# THIEA3000_LIGHTING_BOARD_V2-2.net
KiCad netlist of a schematic drawn in Altium Designer
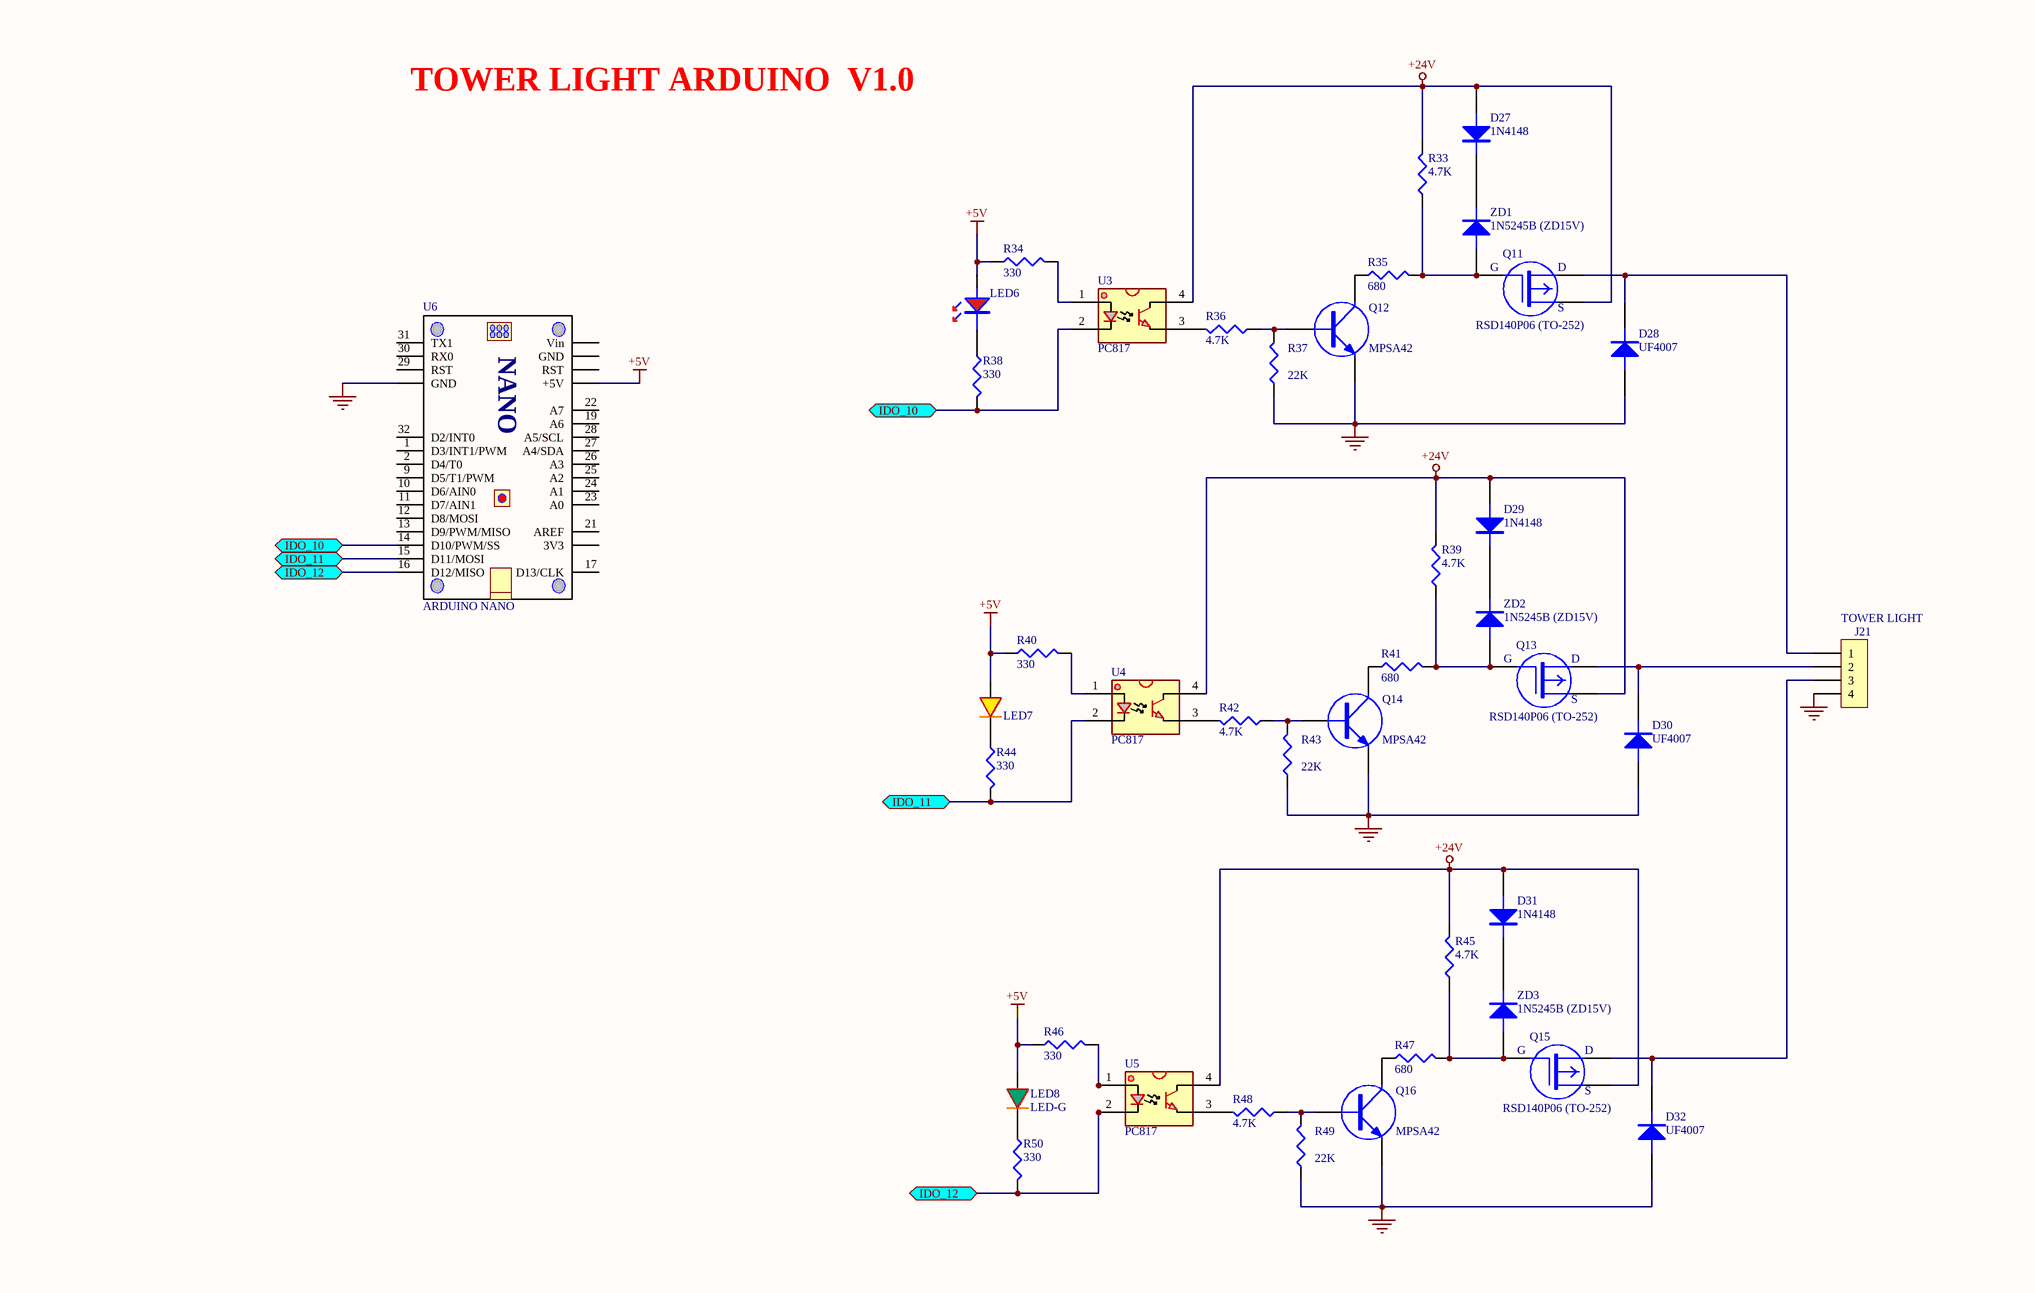
[diagram p0: THIEA3000 LIGHTING BOARD V2-2.SchDoc]

(export (version "E")
  (design (tool "Eeschema 10.0.6"))
  (components
    (comp (ref "D27")
      (value "1N4148")
      (footprint "DIODE 8.5")
      (description "Diode")
      (libsource (lib "*") (part "DIODE"))
    )
    (comp (ref "D28")
      (value "UF4007")
      (footprint "diode 13.0")
      (description "0029-0179-1")
      (libsource (lib "*") (part "DIODE"))
    )
    (comp (ref "D29")
      (value "1N4148")
      (footprint "DIODE 8.5")
      (description "Diode")
      (libsource (lib "*") (part "DIODE"))
    )
    (comp (ref "D30")
      (value "UF4007")
      (footprint "diode 13.0")
      (description "0029-0179-1")
      (libsource (lib "*") (part "DIODE"))
    )
    (comp (ref "D31")
      (value "1N4148")
      (footprint "DIODE 8.5")
      (description "Diode")
      (libsource (lib "*") (part "DIODE"))
    )
    (comp (ref "D32")
      (value "UF4007")
      (footprint "diode 13.0")
      (description "0029-0179-1")
      (libsource (lib "*") (part "DIODE"))
    )
    (comp (ref "J21")
      (value "TOWER LIGHT")
      (footprint "Plug-in TERM 5.0/4P/R")
      (description "0005-0012-5")
      (libsource (lib "*") (part "CON4"))
    )
    (comp (ref "LED6")
      (value "~")
      (footprint "LED 3/2.54/R")
      (description "0302-0042-3")
      (libsource (lib "*") (part "LED-R"))
    )
    (comp (ref "LED7")
      (value "LED-Y")
      (footprint "LED 3/2.54/R")
      (description "0686-0022-4")
      (libsource (lib "Support Project") (part "LED-Y"))
    )
    (comp (ref "LED8")
      (value "LED-G")
      (footprint "LED 5/2.54/R")
      (description "0302-0001-4")
      (libsource (lib "Support Project") (part "LED-G"))
    )
    (comp (ref "Q11")
      (value "RSD140P06 (TO-252)")
      (footprint "TO-252-3")
      (description "0176-0392-4")
      (libsource (lib "*") (part "MOSFET-P1"))
    )
    (comp (ref "Q12")
      (value "MPSA42")
      (footprint "TO-92")
      (description "0123-0670-5")
      (fields (field (name "ALTIUM_UNNAMED_1") "MPSA42"))
      (libsource (lib "*") (part "NPN"))
    )
    (comp (ref "Q13")
      (value "RSD140P06 (TO-252)")
      (footprint "TO-252-3")
      (description "0176-0392-4")
      (libsource (lib "*") (part "MOSFET-P1"))
    )
    (comp (ref "Q14")
      (value "MPSA42")
      (footprint "TO-92")
      (description "0123-0670-5")
      (fields (field (name "ALTIUM_UNNAMED_1") "MPSA42"))
      (libsource (lib "*") (part "NPN"))
    )
    (comp (ref "Q15")
      (value "RSD140P06 (TO-252)")
      (footprint "TO-252-3")
      (description "0176-0392-4")
      (libsource (lib "*") (part "MOSFET-P1"))
    )
    (comp (ref "Q16")
      (value "MPSA42")
      (footprint "TO-92")
      (description "0123-0670-5")
      (fields (field (name "ALTIUM_UNNAMED_1") "MPSA42"))
      (libsource (lib "*") (part "NPN"))
    )
    (comp (ref "R33")
      (value "22K")
      (footprint "RES 1/4")
      (fields (field (name "ALTIUM_UNNAMED_1") "4.7K"))
      (libsource (lib "*") (part "RES1"))
    )
    (comp (ref "R34")
      (value "22K")
      (footprint "RES 1/4")
      (fields (field (name "ALTIUM_UNNAMED_1") "330"))
      (libsource (lib "*") (part "RES1"))
    )
    (comp (ref "R35") (value "680") (footprint "RES 1/4") (libsource (lib "*") (part "RES1")))
    (comp (ref "R36")
      (value "22K")
      (footprint "RES 1/4")
      (fields (field (name "ALTIUM_UNNAMED_1") "4.7K"))
      (libsource (lib "*") (part "RES1"))
    )
    (comp (ref "R37")
      (value "22K")
      (footprint "RES 1/4")
      (fields (field (name "ALTIUM_UNNAMED_1") "22K"))
      (libsource (lib "*") (part "RES1"))
    )
    (comp (ref "R38")
      (value "22K")
      (footprint "RES 1/4")
      (fields (field (name "ALTIUM_UNNAMED_1") "330"))
      (libsource (lib "*") (part "RES1"))
    )
    (comp (ref "R39")
      (value "22K")
      (footprint "RES 1/4")
      (fields (field (name "ALTIUM_UNNAMED_1") "4.7K"))
      (libsource (lib "*") (part "RES1"))
    )
    (comp (ref "R40")
      (value "22K")
      (footprint "RES 1/4")
      (fields (field (name "ALTIUM_UNNAMED_1") "330"))
      (libsource (lib "*") (part "RES1"))
    )
    (comp (ref "R41") (value "680") (footprint "RES 1/4") (libsource (lib "*") (part "RES1")))
    (comp (ref "R42")
      (value "22K")
      (footprint "RES 1/4")
      (fields (field (name "ALTIUM_UNNAMED_1") "4.7K"))
      (libsource (lib "*") (part "RES1"))
    )
    (comp (ref "R43")
      (value "22K")
      (footprint "RES 1/4")
      (fields (field (name "ALTIUM_UNNAMED_1") "22K"))
      (libsource (lib "*") (part "RES1"))
    )
    (comp (ref "R44")
      (value "22K")
      (footprint "RES 1/4")
      (fields (field (name "ALTIUM_UNNAMED_1") "330"))
      (libsource (lib "*") (part "RES1"))
    )
    (comp (ref "R45")
      (value "22K")
      (footprint "RES 1/4")
      (fields (field (name "ALTIUM_UNNAMED_1") "4.7K"))
      (libsource (lib "*") (part "RES1"))
    )
    (comp (ref "R46")
      (value "22K")
      (footprint "RES 1/4")
      (fields (field (name "ALTIUM_UNNAMED_1") "330"))
      (libsource (lib "*") (part "RES1"))
    )
    (comp (ref "R47") (value "680") (footprint "RES 1/4") (libsource (lib "*") (part "RES1")))
    (comp (ref "R48")
      (value "22K")
      (footprint "RES 1/4")
      (fields (field (name "ALTIUM_UNNAMED_1") "4.7K"))
      (libsource (lib "*") (part "RES1"))
    )
    (comp (ref "R49")
      (value "22K")
      (footprint "RES 1/4")
      (fields (field (name "ALTIUM_UNNAMED_1") "22K"))
      (libsource (lib "*") (part "RES1"))
    )
    (comp (ref "R50")
      (value "22K")
      (footprint "RES 1/4")
      (fields (field (name "ALTIUM_UNNAMED_1") "330"))
      (libsource (lib "*") (part "RES1"))
    )
    (comp (ref "U3")
      (value "PC817")
      (footprint "DIP-4L")
      (libsource (lib "Support Project") (part "OPTO TRANSISTOR"))
    )
    (comp (ref "U4")
      (value "PC817")
      (footprint "DIP-4L")
      (libsource (lib "Support Project") (part "OPTO TRANSISTOR"))
    )
    (comp (ref "U5")
      (value "PC817")
      (footprint "DIP-4L")
      (libsource (lib "Support Project") (part "OPTO TRANSISTOR"))
    )
    (comp (ref "U6")
      (value "ARDUINO NANO")
      (footprint "ARDUINO Nano")
      (libsource (lib "Support Project") (part "ARDUINO NANO"))
    )
    (comp (ref "ZD1")
      (value "1N5245B (ZD15V)")
      (footprint "DIODE 8.5")
      (description "0135-0081-3")
      (libsource (lib "*") (part "DIODE"))
    )
    (comp (ref "ZD2")
      (value "1N5245B (ZD15V)")
      (footprint "DIODE 8.5")
      (description "0135-0081-3")
      (libsource (lib "*") (part "DIODE"))
    )
    (comp (ref "ZD3")
      (value "1N5245B (ZD15V)")
      (footprint "DIODE 8.5")
      (description "0135-0081-3")
      (libsource (lib "*") (part "DIODE"))
    )
  )
  (nets
    (net (code "1") (name "+5V") (class "Default")
      (node (ref "LED6") (pin "A") (pintype "passive"))
      (node (ref "LED7") (pin "A") (pinfunction "A_A") (pintype "passive"))
      (node (ref "LED8") (pin "A") (pinfunction "A_A") (pintype "passive"))
      (node (ref "R34") (pin "1") (pintype "passive"))
      (node (ref "R40") (pin "1") (pintype "passive"))
      (node (ref "R46") (pin "1") (pintype "passive"))
      (node (ref "U6") (pin "+5V") (pinfunction "+5V_+5V") (pintype "passive"))
    )
    (net (code "2") (name "+24V") (class "Default")
      (node (ref "D27") (pin "1") (pinfunction "A_1") (pintype "passive"))
      (node (ref "D29") (pin "1") (pinfunction "A_1") (pintype "passive"))
      (node (ref "D31") (pin "1") (pinfunction "A_1") (pintype "passive"))
      (node (ref "Q11") (pin "2") (pinfunction "D_2") (pintype "passive"))
      (node (ref "Q13") (pin "2") (pinfunction "D_2") (pintype "passive"))
      (node (ref "Q15") (pin "2") (pinfunction "D_2") (pintype "passive"))
      (node (ref "R33") (pin "2") (pintype "passive"))
      (node (ref "R39") (pin "2") (pintype "passive"))
      (node (ref "R45") (pin "2") (pintype "passive"))
      (node (ref "U3") (pin "4") (pinfunction "C_4") (pintype "passive"))
      (node (ref "U4") (pin "4") (pinfunction "C_4") (pintype "passive"))
      (node (ref "U5") (pin "4") (pinfunction "C_4") (pintype "passive"))
    )
    (net (code "3") (name "/IDO_10") (class "Default")
      (node (ref "R38") (pin "2") (pintype "passive"))
      (node (ref "U3") (pin "2") (pinfunction "K_2") (pintype "passive"))
      (node (ref "U6") (pin "14") (pinfunction "D10/PWM/SS_14") (pintype "passive"))
    )
    (net (code "4") (name "/IDO_11") (class "Default")
      (node (ref "R44") (pin "2") (pintype "passive"))
      (node (ref "U4") (pin "2") (pinfunction "K_2") (pintype "passive"))
      (node (ref "U6") (pin "15") (pinfunction "D11/MOSI_15") (pintype "passive"))
    )
    (net (code "5") (name "/IDO_12") (class "Default")
      (node (ref "R50") (pin "2") (pintype "passive"))
      (node (ref "U5") (pin "2") (pinfunction "K_2") (pintype "passive"))
      (node (ref "U6") (pin "16") (pinfunction "D12/MISO_16") (pintype "passive"))
    )
    (net (code "6") (name "GND1") (class "Default")
      (node (ref "D28") (pin "1") (pinfunction "A_1") (pintype "passive"))
      (node (ref "D30") (pin "1") (pinfunction "A_1") (pintype "passive"))
      (node (ref "D32") (pin "1") (pinfunction "A_1") (pintype "passive"))
      (node (ref "J21") (pin "4") (pinfunction "4_4") (pintype "passive"))
      (node (ref "Q12") (pin "3") (pinfunction "E_3") (pintype "passive"))
      (node (ref "Q14") (pin "3") (pinfunction "E_3") (pintype "passive"))
      (node (ref "Q16") (pin "3") (pinfunction "E_3") (pintype "passive"))
      (node (ref "R37") (pin "1") (pintype "passive"))
      (node (ref "R43") (pin "1") (pintype "passive"))
      (node (ref "R49") (pin "1") (pintype "passive"))
      (node (ref "U6") (pin "GND") (pinfunction "GND_GND") (pintype "passive"))
    )
    (net (code "7") (name "Net-(D27-K)") (class "Default")
      (node (ref "D27") (pin "2") (pinfunction "K_2") (pintype "passive"))
      (node (ref "ZD1") (pin "2") (pinfunction "K_2") (pintype "passive"))
    )
    (net (code "8") (name "Net-(D28-K)") (class "Default")
      (node (ref "D28") (pin "2") (pinfunction "K_2") (pintype "passive"))
      (node (ref "J21") (pin "1") (pinfunction "1_1") (pintype "passive"))
      (node (ref "Q11") (pin "3") (pinfunction "S_3") (pintype "passive"))
    )
    (net (code "9") (name "Net-(D29-K)") (class "Default")
      (node (ref "D29") (pin "2") (pinfunction "K_2") (pintype "passive"))
      (node (ref "ZD2") (pin "2") (pinfunction "K_2") (pintype "passive"))
    )
    (net (code "10") (name "Net-(D30-K)") (class "Default")
      (node (ref "D30") (pin "2") (pinfunction "K_2") (pintype "passive"))
      (node (ref "J21") (pin "2") (pinfunction "2_2") (pintype "passive"))
      (node (ref "Q13") (pin "3") (pinfunction "S_3") (pintype "passive"))
    )
    (net (code "11") (name "Net-(D31-K)") (class "Default")
      (node (ref "D31") (pin "2") (pinfunction "K_2") (pintype "passive"))
      (node (ref "ZD3") (pin "2") (pinfunction "K_2") (pintype "passive"))
    )
    (net (code "12") (name "Net-(D32-K)") (class "Default")
      (node (ref "D32") (pin "2") (pinfunction "K_2") (pintype "passive"))
      (node (ref "J21") (pin "3") (pinfunction "3_3") (pintype "passive"))
      (node (ref "Q15") (pin "3") (pinfunction "S_3") (pintype "passive"))
    )
    (net (code "13") (name "Net-(LED6-PadK)") (class "Default")
      (node (ref "LED6") (pin "K") (pintype "passive"))
      (node (ref "R38") (pin "1") (pintype "passive"))
    )
    (net (code "14") (name "Net-(LED7-PadK)") (class "Default")
      (node (ref "LED7") (pin "K") (pinfunction "K_K") (pintype "passive"))
      (node (ref "R44") (pin "1") (pintype "passive"))
    )
    (net (code "15") (name "Net-(LED8-PadK)") (class "Default")
      (node (ref "LED8") (pin "K") (pinfunction "K_K") (pintype "passive"))
      (node (ref "R50") (pin "1") (pintype "passive"))
    )
    (net (code "16") (name "Net-(Q11-G)") (class "Default")
      (node (ref "Q11") (pin "1") (pinfunction "G_1") (pintype "passive"))
      (node (ref "R33") (pin "1") (pintype "passive"))
      (node (ref "R35") (pin "2") (pintype "passive"))
      (node (ref "ZD1") (pin "1") (pinfunction "A_1") (pintype "passive"))
    )
    (net (code "17") (name "Net-(Q12-B)") (class "Default")
      (node (ref "Q12") (pin "1") (pinfunction "B_1") (pintype "passive"))
      (node (ref "R36") (pin "1") (pintype "passive"))
      (node (ref "R37") (pin "2") (pintype "passive"))
    )
    (net (code "18") (name "Net-(Q12-C)") (class "Default")
      (node (ref "Q12") (pin "2") (pinfunction "C_2") (pintype "passive"))
      (node (ref "R35") (pin "1") (pintype "passive"))
    )
    (net (code "19") (name "Net-(Q13-G)") (class "Default")
      (node (ref "Q13") (pin "1") (pinfunction "G_1") (pintype "passive"))
      (node (ref "R39") (pin "1") (pintype "passive"))
      (node (ref "R41") (pin "2") (pintype "passive"))
      (node (ref "ZD2") (pin "1") (pinfunction "A_1") (pintype "passive"))
    )
    (net (code "20") (name "Net-(Q14-B)") (class "Default")
      (node (ref "Q14") (pin "1") (pinfunction "B_1") (pintype "passive"))
      (node (ref "R42") (pin "1") (pintype "passive"))
      (node (ref "R43") (pin "2") (pintype "passive"))
    )
    (net (code "21") (name "Net-(Q14-C)") (class "Default")
      (node (ref "Q14") (pin "2") (pinfunction "C_2") (pintype "passive"))
      (node (ref "R41") (pin "1") (pintype "passive"))
    )
    (net (code "22") (name "Net-(Q15-G)") (class "Default")
      (node (ref "Q15") (pin "1") (pinfunction "G_1") (pintype "passive"))
      (node (ref "R45") (pin "1") (pintype "passive"))
      (node (ref "R47") (pin "2") (pintype "passive"))
      (node (ref "ZD3") (pin "1") (pinfunction "A_1") (pintype "passive"))
    )
    (net (code "23") (name "Net-(Q16-B)") (class "Default")
      (node (ref "Q16") (pin "1") (pinfunction "B_1") (pintype "passive"))
      (node (ref "R48") (pin "1") (pintype "passive"))
      (node (ref "R49") (pin "2") (pintype "passive"))
    )
    (net (code "24") (name "Net-(Q16-C)") (class "Default")
      (node (ref "Q16") (pin "2") (pinfunction "C_2") (pintype "passive"))
      (node (ref "R47") (pin "1") (pintype "passive"))
    )
    (net (code "25") (name "Net-(U3-A)") (class "Default")
      (node (ref "R34") (pin "2") (pintype "passive"))
      (node (ref "U3") (pin "1") (pinfunction "A_1") (pintype "passive"))
    )
    (net (code "26") (name "Net-(U3-E)") (class "Default")
      (node (ref "R36") (pin "2") (pintype "passive"))
      (node (ref "U3") (pin "3") (pinfunction "E_3") (pintype "passive"))
    )
    (net (code "27") (name "Net-(U4-A)") (class "Default")
      (node (ref "R40") (pin "2") (pintype "passive"))
      (node (ref "U4") (pin "1") (pinfunction "A_1") (pintype "passive"))
    )
    (net (code "28") (name "Net-(U4-E)") (class "Default")
      (node (ref "R42") (pin "2") (pintype "passive"))
      (node (ref "U4") (pin "3") (pinfunction "E_3") (pintype "passive"))
    )
    (net (code "29") (name "Net-(U5-A)") (class "Default")
      (node (ref "R46") (pin "2") (pintype "passive"))
      (node (ref "U5") (pin "1") (pinfunction "A_1") (pintype "passive"))
    )
    (net (code "30") (name "Net-(U5-E)") (class "Default")
      (node (ref "R48") (pin "2") (pintype "passive"))
      (node (ref "U5") (pin "3") (pinfunction "E_3") (pintype "passive"))
    )
    (net (code "31") (name "unconnected-(U6-A0-Pad23)") (class "Default")
      (node (ref "U6") (pin "23") (pinfunction "A0_23") (pintype "passive"))
    )
    (net (code "32") (name "unconnected-(U6-A1-Pad24)") (class "Default")
      (node (ref "U6") (pin "24") (pinfunction "A1_24") (pintype "passive"))
    )
    (net (code "33") (name "unconnected-(U6-A2-Pad25)") (class "Default")
      (node (ref "U6") (pin "25") (pinfunction "A2_25") (pintype "passive"))
    )
    (net (code "34") (name "unconnected-(U6-A3-Pad26)") (class "Default")
      (node (ref "U6") (pin "26") (pinfunction "A3_26") (pintype "passive"))
    )
    (net (code "35") (name "unconnected-(U6-A4{slash}SDA-Pad27)") (class "Default")
      (node (ref "U6") (pin "27") (pinfunction "A4/SDA_27") (pintype "passive"))
    )
    (net (code "36") (name "unconnected-(U6-A5{slash}SCL-Pad28)") (class "Default")
      (node (ref "U6") (pin "28") (pinfunction "A5/SCL_28") (pintype "passive"))
    )
    (net (code "37") (name "unconnected-(U6-A6-Pad19)") (class "Default")
      (node (ref "U6") (pin "19") (pinfunction "A6_19") (pintype "passive"))
    )
    (net (code "38") (name "unconnected-(U6-A7-Pad22)") (class "Default")
      (node (ref "U6") (pin "22") (pinfunction "A7_22") (pintype "passive"))
    )
    (net (code "39") (name "unconnected-(U6-AREF-Pad21)") (class "Default")
      (node (ref "U6") (pin "21") (pinfunction "AREF_21") (pintype "passive"))
    )
    (net (code "40") (name "unconnected-(U6-D2{slash}INT0-Pad32)") (class "Default")
      (node (ref "U6") (pin "32") (pinfunction "D2/INT0_32") (pintype "passive"))
    )
    (net (code "41") (name "unconnected-(U6-D3{slash}INT1{slash}PWM-Pad1)") (class "Default")
      (node (ref "U6") (pin "1") (pinfunction "D3/INT1/PWM_1") (pintype "passive"))
    )
    (net (code "42") (name "unconnected-(U6-D4{slash}T0-Pad2)") (class "Default")
      (node (ref "U6") (pin "2") (pinfunction "D4/T0_2") (pintype "passive"))
    )
    (net (code "43") (name "unconnected-(U6-D5{slash}T1{slash}PWM-Pad9)") (class "Default")
      (node (ref "U6") (pin "9") (pinfunction "D5/T1/PWM_9") (pintype "passive"))
    )
    (net (code "44") (name "unconnected-(U6-D6{slash}AIN0-Pad10)") (class "Default")
      (node (ref "U6") (pin "10") (pinfunction "D6/AIN0_10") (pintype "passive"))
    )
    (net (code "45") (name "unconnected-(U6-D7{slash}AIN1-Pad11)") (class "Default")
      (node (ref "U6") (pin "11") (pinfunction "D7/AIN1_11") (pintype "passive"))
    )
    (net (code "46") (name "unconnected-(U6-D8{slash}MOSI-Pad12)") (class "Default")
      (node (ref "U6") (pin "12") (pinfunction "D8/MOSI_12") (pintype "passive"))
    )
    (net (code "47") (name "unconnected-(U6-D9{slash}PWM{slash}MISO-Pad13)") (class "Default")
      (node (ref "U6") (pin "13") (pinfunction "D9/PWM/MISO_13") (pintype "passive"))
    )
    (net (code "48") (name "unconnected-(U6-D13{slash}CLK-Pad17)") (class "Default")
      (node (ref "U6") (pin "17") (pinfunction "D13/CLK_17") (pintype "passive"))
    )
    (net (code "49") (name "unconnected-(U6-Pad3V3)") (class "Default")
      (node (ref "U6") (pin "3V3") (pinfunction "3V3_3V3") (pintype "passive"))
    )
    (net (code "50") (name "unconnected-(U6-PadGND)") (class "Default")
      (node (ref "U6") (pin "GND") (pinfunction "GND_GND") (pintype "passive"))
    )
    (net (code "51") (name "unconnected-(U6-PadRST)") (class "Default")
      (node (ref "U6") (pin "RST") (pinfunction "RST_RST") (pintype "passive"))
    )
    (net (code "52") (name "unconnected-(U6-PadVin)") (class "Default")
      (node (ref "U6") (pin "Vin") (pinfunction "Vin_Vin") (pintype "passive"))
    )
    (net (code "53") (name "unconnected-(U6-RST-Pad29)") (class "Default")
      (node (ref "U6") (pin "29") (pinfunction "RST_29") (pintype "passive"))
    )
    (net (code "54") (name "unconnected-(U6-RX0-Pad30)") (class "Default")
      (node (ref "U6") (pin "30") (pinfunction "RX0_30") (pintype "passive"))
    )
    (net (code "55") (name "unconnected-(U6-TX1-Pad31)") (class "Default")
      (node (ref "U6") (pin "31") (pinfunction "TX1_31") (pintype "passive"))
    )
  )
)
